# MTX_Tap_an_er_V14_Nopoti.net
KiCad netlist of a schematic drawn in EAGLE
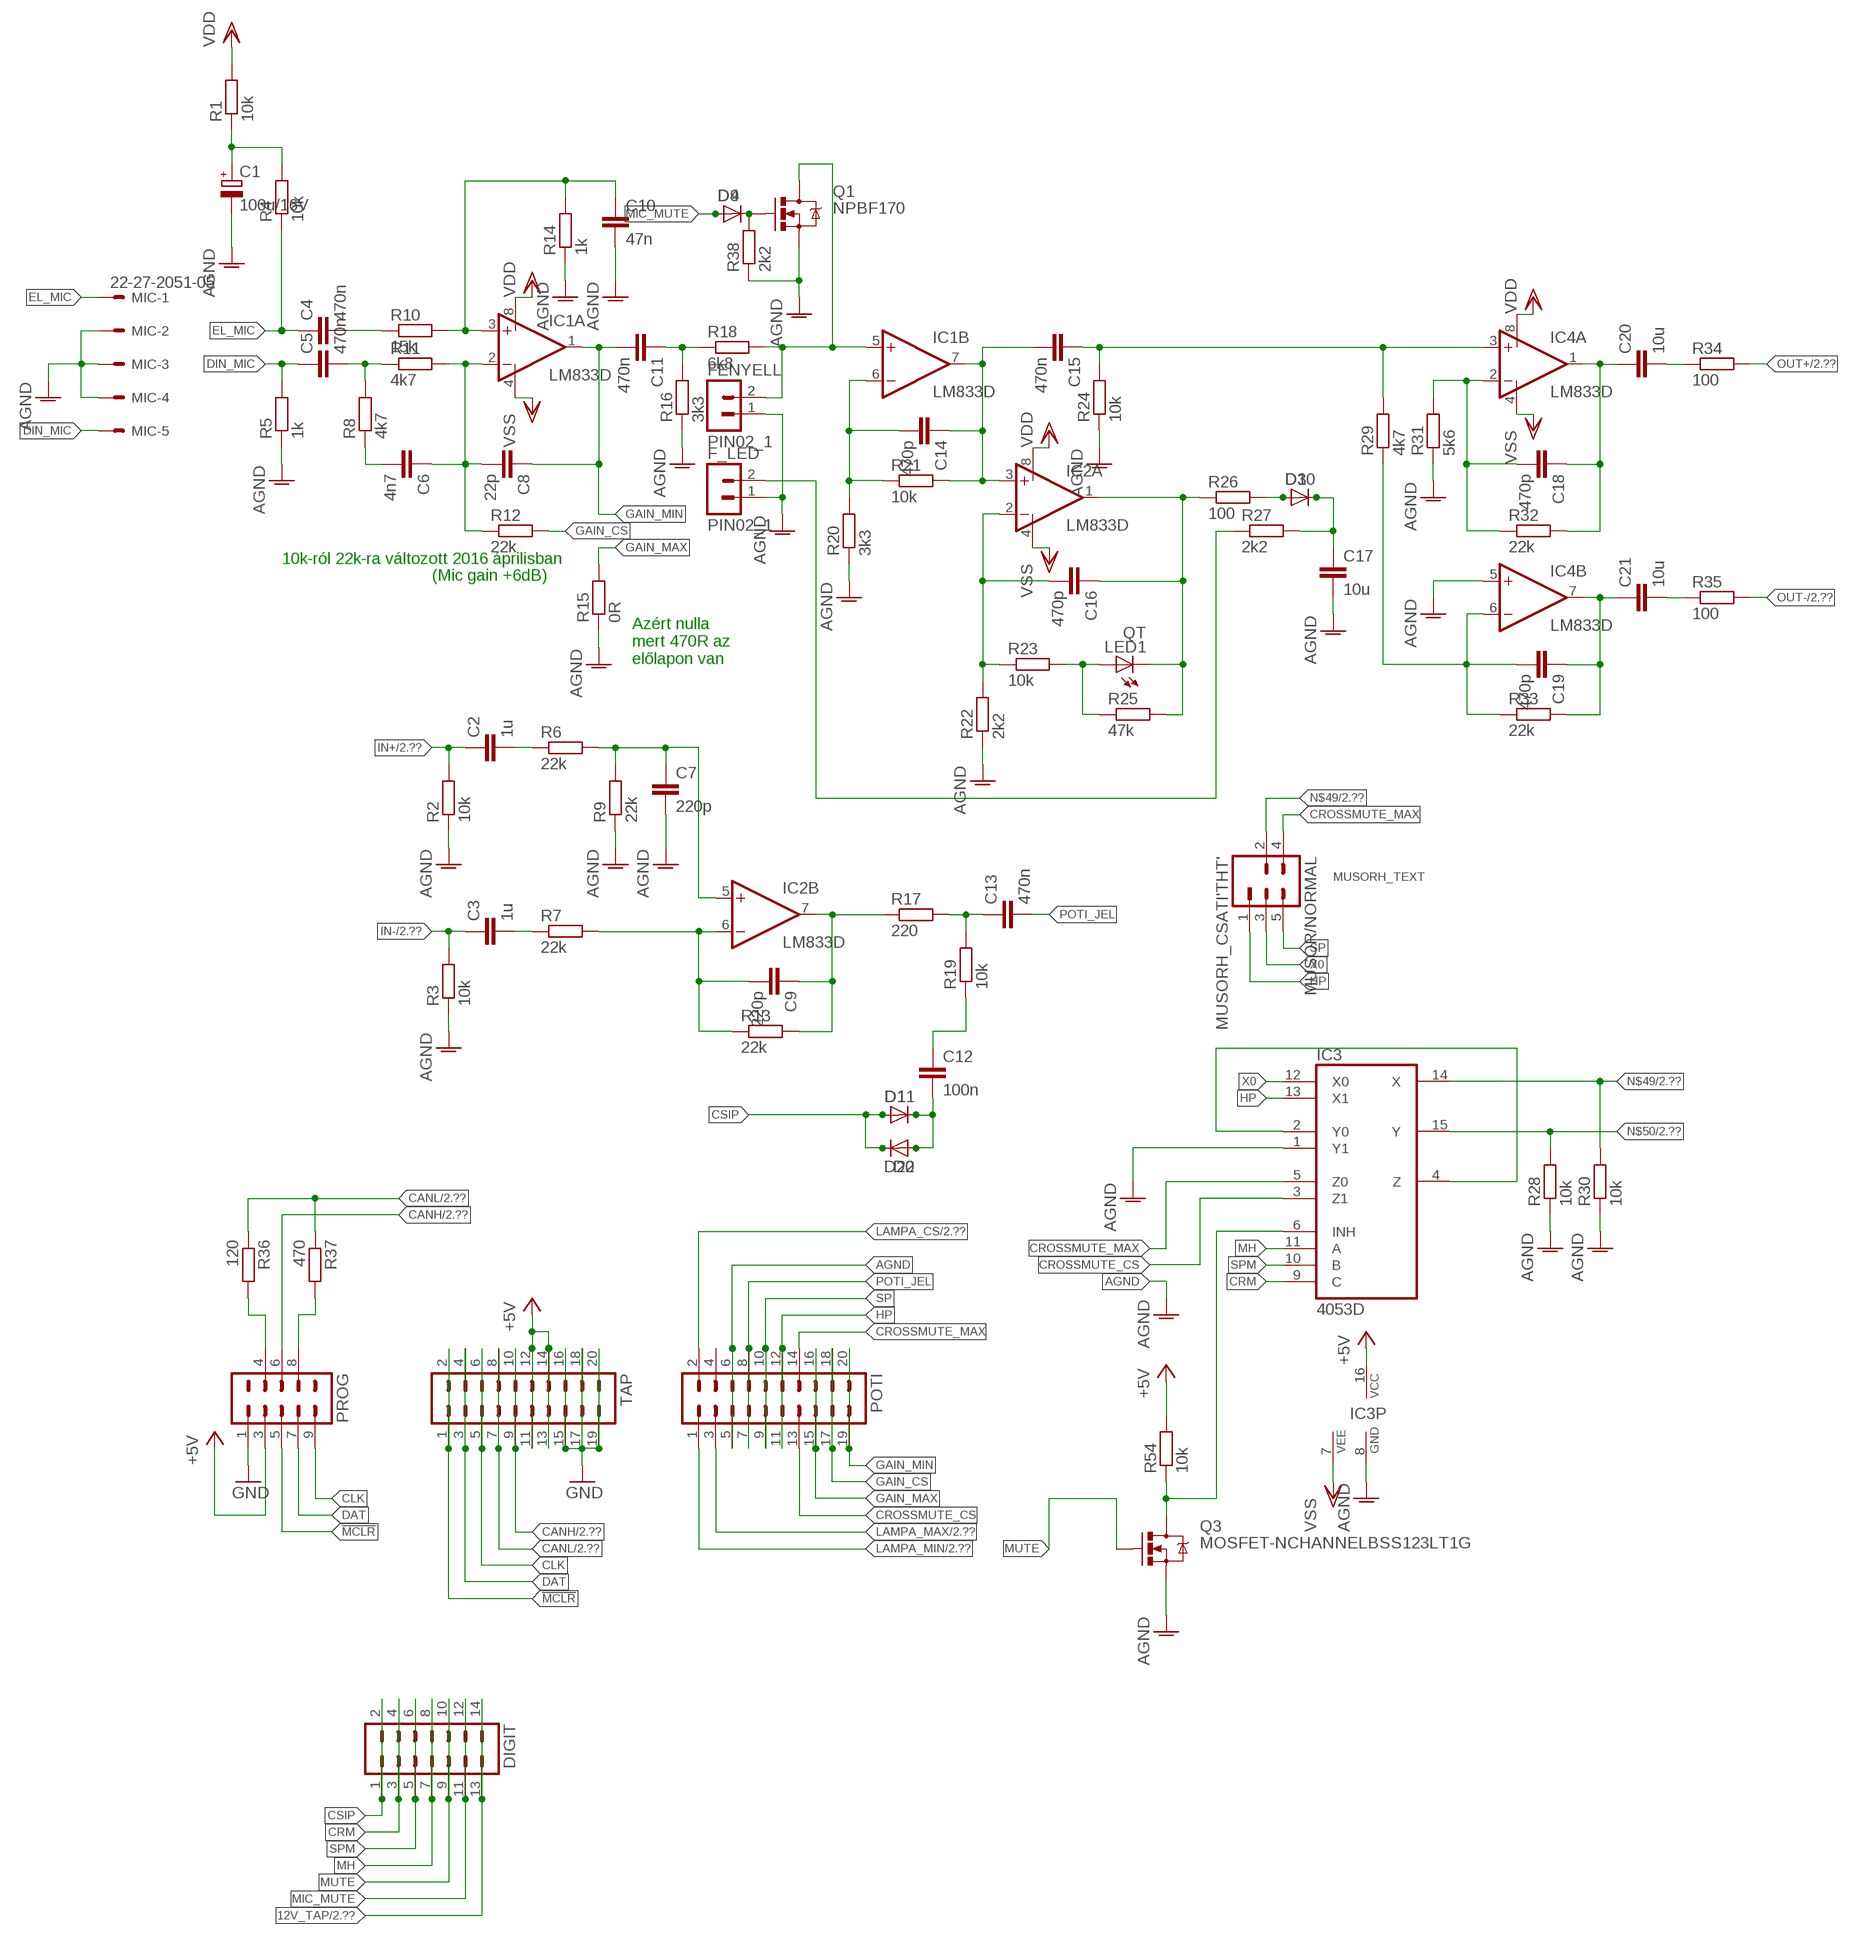
[diagram p0: schematic, sheet 1]
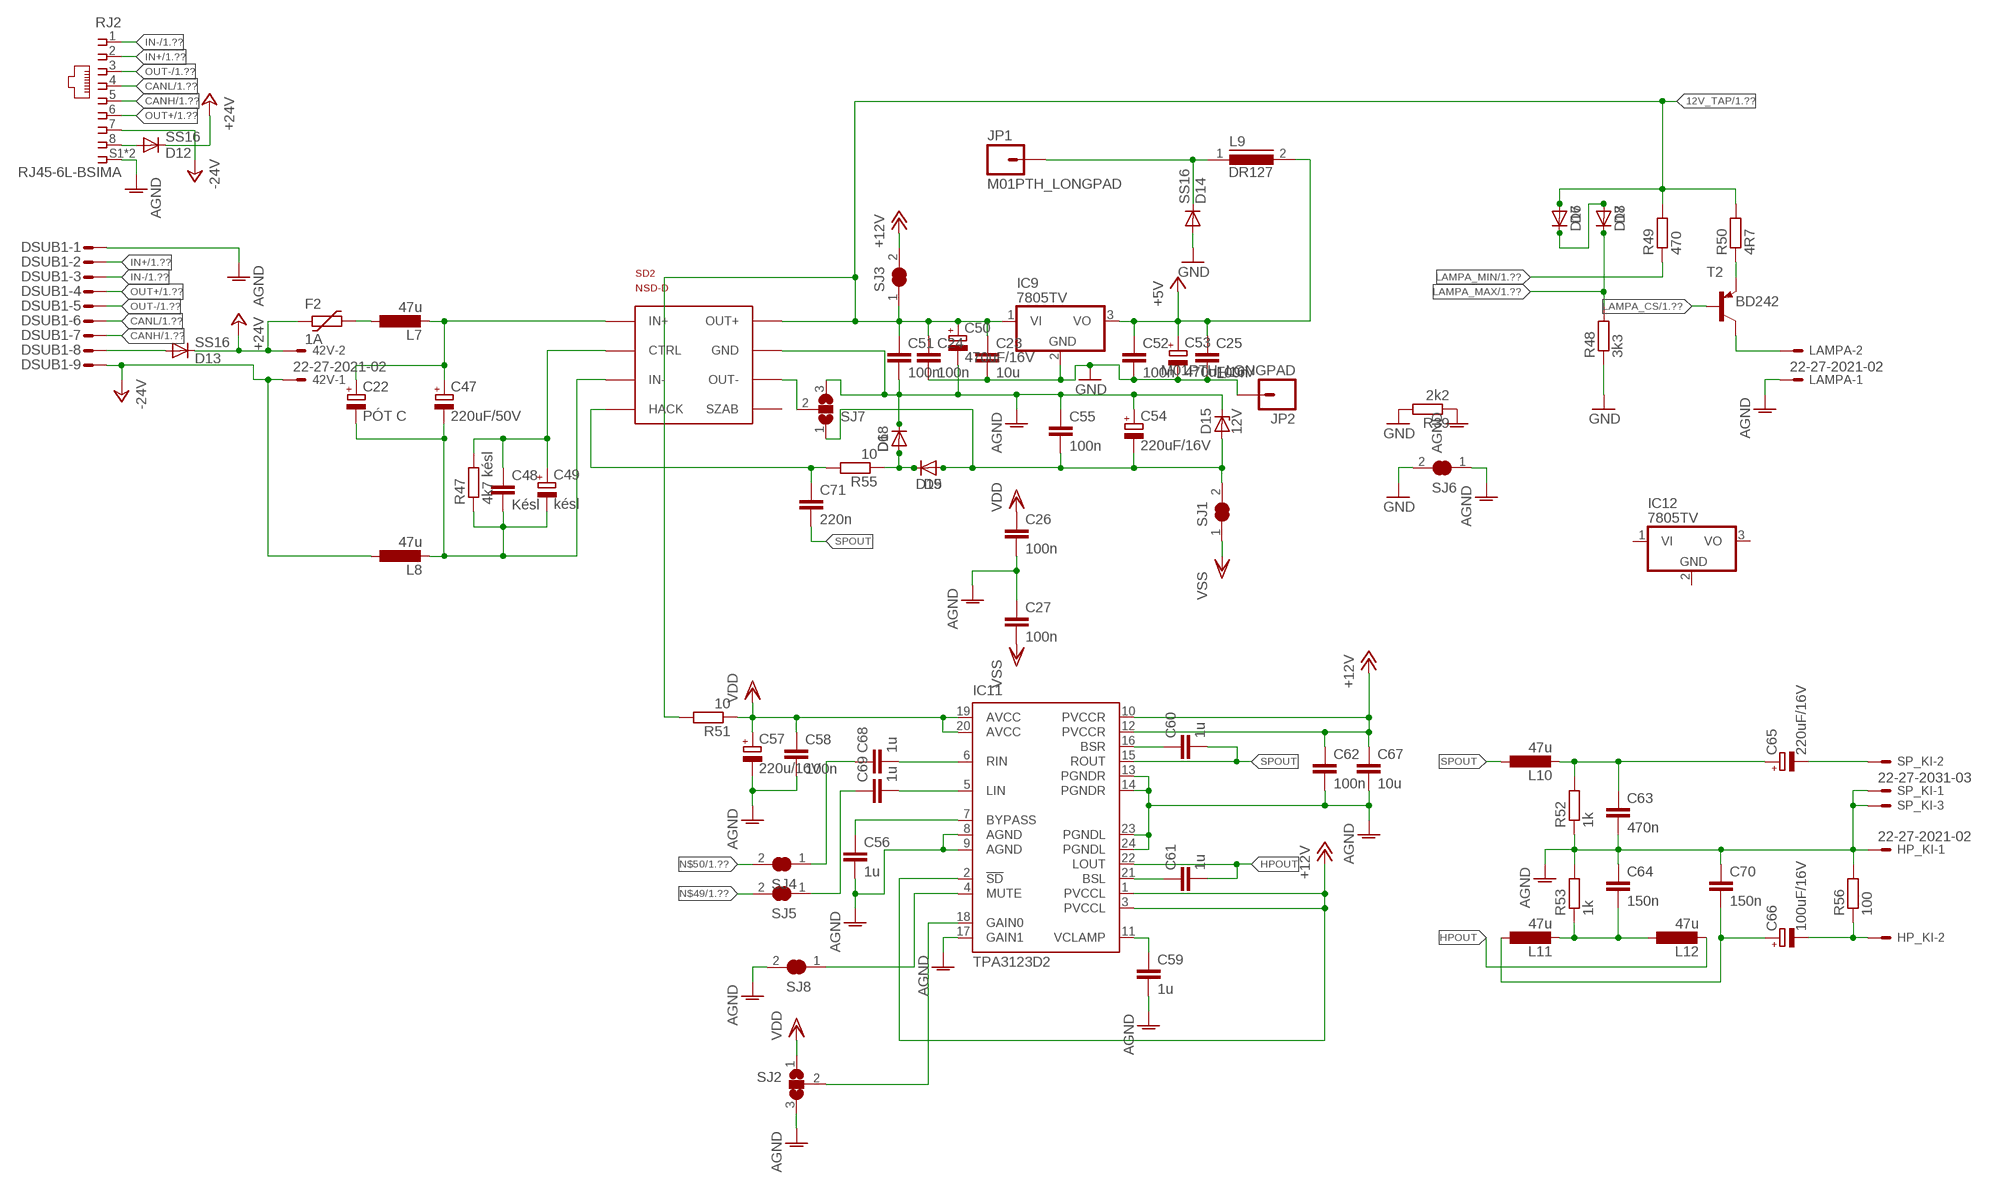
[diagram p1: schematic, sheet 2]

(export (version "E")
  (design (tool "Eeschema 10.0.6"))
  (components
    (comp (ref "C1")
      (value "100u/16V")
      (footprint "eagle-import:E2,5-5")
      (libsource (lib "eagle-import") (part "CPOL-EUE2.5-5"))
    )
    (comp (ref "C2")
      (value "1u")
      (footprint "eagle-import:C0805")
      (libsource (lib "eagle-import") (part "C-EUC0805"))
    )
    (comp (ref "C3")
      (value "1u")
      (footprint "eagle-import:C0805")
      (libsource (lib "eagle-import") (part "C-EUC0805"))
    )
    (comp (ref "C4")
      (value "470n")
      (footprint "eagle-import:C0805")
      (libsource (lib "eagle-import") (part "C-EUC0805"))
    )
    (comp (ref "C5")
      (value "470n")
      (footprint "eagle-import:C0805")
      (libsource (lib "eagle-import") (part "C-EUC0805"))
    )
    (comp (ref "C6")
      (value "4n7")
      (footprint "eagle-import:C0805")
      (libsource (lib "eagle-import") (part "C-EUC0805"))
    )
    (comp (ref "C7")
      (value "220p")
      (footprint "eagle-import:C0805")
      (libsource (lib "eagle-import") (part "C-EUC0805"))
    )
    (comp (ref "C8")
      (value "22p")
      (footprint "eagle-import:C0805")
      (libsource (lib "eagle-import") (part "C-EUC0805"))
    )
    (comp (ref "C9")
      (value "220p")
      (footprint "eagle-import:C0805")
      (libsource (lib "eagle-import") (part "C-EUC0805"))
    )
    (comp (ref "C10")
      (value "47n")
      (footprint "eagle-import:C0805")
      (libsource (lib "eagle-import") (part "C-EUC0805"))
    )
    (comp (ref "C11")
      (value "470n")
      (footprint "eagle-import:C0805")
      (libsource (lib "eagle-import") (part "C-EUC0805"))
    )
    (comp (ref "C12")
      (value "100n")
      (footprint "eagle-import:C0805")
      (libsource (lib "eagle-import") (part "C-EUC0805"))
    )
    (comp (ref "C13")
      (value "470n")
      (footprint "eagle-import:C0805")
      (libsource (lib "eagle-import") (part "C-EUC0805"))
    )
    (comp (ref "C14")
      (value "470p")
      (footprint "eagle-import:C0805")
      (libsource (lib "eagle-import") (part "C-EUC0805"))
    )
    (comp (ref "C15")
      (value "470n")
      (footprint "eagle-import:C0805")
      (libsource (lib "eagle-import") (part "C-EUC0805"))
    )
    (comp (ref "C16")
      (value "470p")
      (footprint "eagle-import:C0805")
      (libsource (lib "eagle-import") (part "C-EUC0805"))
    )
    (comp (ref "C17")
      (value "10u")
      (footprint "eagle-import:C0805")
      (libsource (lib "eagle-import") (part "C-EUC0805"))
    )
    (comp (ref "C18")
      (value "470p")
      (footprint "eagle-import:C0805")
      (libsource (lib "eagle-import") (part "C-EUC0805"))
    )
    (comp (ref "C19")
      (value "470p")
      (footprint "eagle-import:C0805")
      (libsource (lib "eagle-import") (part "C-EUC0805"))
    )
    (comp (ref "C20")
      (value "10u")
      (footprint "eagle-import:C0805")
      (libsource (lib "eagle-import") (part "C-EUC0805"))
    )
    (comp (ref "C21")
      (value "10u")
      (footprint "eagle-import:C0805")
      (libsource (lib "eagle-import") (part "C-EUC0805"))
    )
    (comp (ref "D1")
      (value "1N4148")
      (footprint "eagle-import:DGLASSSMD")
      (libsource (lib "eagle-import") (part "DGLASSMD"))
    )
    (comp (ref "D2")
      (value "1N4148")
      (footprint "eagle-import:DGLASSSMD")
      (libsource (lib "eagle-import") (part "DGLASSMD"))
    )
    (comp (ref "D3")
      (value "1N4148")
      (footprint "eagle-import:DGLASSSMD")
      (libsource (lib "eagle-import") (part "DGLASSMD"))
    )
    (comp (ref "D4")
      (value "1N4148")
      (footprint "eagle-import:DGLASSSMD")
      (libsource (lib "eagle-import") (part "DGLASSMD"))
    )
    (comp (ref "D9")
      (value "D0805")
      (footprint "eagle-import:D0805")
      (libsource (lib "eagle-import") (part "D0805"))
    )
    (comp (ref "D10")
      (value "D0805")
      (footprint "eagle-import:D0805")
      (libsource (lib "eagle-import") (part "D0805"))
    )
    (comp (ref "D11")
      (value "D0805")
      (footprint "eagle-import:D0805")
      (libsource (lib "eagle-import") (part "D0805"))
    )
    (comp (ref "D20")
      (value "D0805")
      (footprint "eagle-import:D0805")
      (libsource (lib "eagle-import") (part "D0805"))
    )
    (comp (ref "DIGIT")
      (value "MA07-2")
      (footprint "eagle-import:MA07-2")
      (libsource (lib "eagle-import") (part "MA07-2"))
    )
    (comp (ref "FENYELL")
      (value "PIN02_1")
      (footprint "eagle-import:PIN02_1")
      (libsource (lib "eagle-import") (part "PIN02_1"))
    )
    (comp (ref "F_LED")
      (value "PIN02_1")
      (footprint "eagle-import:PIN02_1")
      (libsource (lib "eagle-import") (part "PIN02_1"))
    )
    (comp (ref "IC1")
      (value "LM833D")
      (footprint "eagle-import:SO08")
      (libsource (lib "eagle-import") (part "LM833D"))
    )
    (comp (ref "IC2")
      (value "LM833D")
      (footprint "eagle-import:SO08")
      (libsource (lib "eagle-import") (part "LM833D"))
    )
    (comp (ref "IC3")
      (value "4053D")
      (footprint "eagle-import:SO16")
      (libsource (lib "eagle-import") (part "4053D"))
    )
    (comp (ref "IC4")
      (value "LM833D")
      (footprint "eagle-import:SO08")
      (libsource (lib "eagle-import") (part "LM833D"))
    )
    (comp (ref "LED1")
      (value "QT")
      (footprint "eagle-import:LED3MM")
      (libsource (lib "eagle-import") (part "LED3MM"))
    )
    (comp (ref "MIC")
      (value "22-27-2051-05")
      (footprint "eagle-import:6410-05")
      (libsource (lib "eagle-import") (part "22-?-0527-2051"))
    )
    (comp (ref "MUSOR/NORMAL")
      (value "MUSORH_CSATI'THT'")
      (footprint "eagle-import:MUSORH_CSATI")
      (libsource (lib "eagle-import") (part "MUSORH_CSATI'THT'"))
    )
    (comp (ref "POTI")
      (value "MA10-2")
      (footprint "eagle-import:MA10-2")
      (libsource (lib "eagle-import") (part "MA10-2"))
    )
    (comp (ref "PROG")
      (value "CN_CANTAN")
      (footprint "eagle-import:CN_CANTAN")
      (libsource (lib "eagle-import") (part "CN_CANTAN"))
    )
    (comp (ref "Q1")
      (value "NPBF170")
      (footprint "eagle-import:SOT23")
      (libsource (lib "eagle-import") (part "MOSFET-NCHANNELBSS138"))
    )
    (comp (ref "Q3")
      (value "MOSFET-NCHANNELBSS123LT1G")
      (footprint "eagle-import:SOT23")
      (libsource (lib "eagle-import") (part "MOSFET-NCHANNELBSS123LT1G"))
    )
    (comp (ref "R1")
      (value "10k")
      (footprint "eagle-import:R0805")
      (libsource (lib "eagle-import") (part "R-EU_R0805"))
    )
    (comp (ref "R2")
      (value "10k")
      (footprint "eagle-import:R0805")
      (libsource (lib "eagle-import") (part "R-EU_R0805"))
    )
    (comp (ref "R3")
      (value "10k")
      (footprint "eagle-import:R0805")
      (libsource (lib "eagle-import") (part "R-EU_R0805"))
    )
    (comp (ref "R4")
      (value "10k")
      (footprint "eagle-import:R0805")
      (libsource (lib "eagle-import") (part "R-EU_R0805"))
    )
    (comp (ref "R5")
      (value "1k")
      (footprint "eagle-import:R0805")
      (libsource (lib "eagle-import") (part "R-EU_R0805"))
    )
    (comp (ref "R6")
      (value "22k")
      (footprint "eagle-import:R0805")
      (libsource (lib "eagle-import") (part "R-EU_R0805"))
    )
    (comp (ref "R7")
      (value "22k")
      (footprint "eagle-import:R0805")
      (libsource (lib "eagle-import") (part "R-EU_R0805"))
    )
    (comp (ref "R8")
      (value "4k7")
      (footprint "eagle-import:R0805")
      (libsource (lib "eagle-import") (part "R-EU_R0805"))
    )
    (comp (ref "R9")
      (value "22k")
      (footprint "eagle-import:R0805")
      (libsource (lib "eagle-import") (part "R-EU_R0805"))
    )
    (comp (ref "R10")
      (value "15k")
      (footprint "eagle-import:R0805")
      (libsource (lib "eagle-import") (part "R-EU_R0805"))
    )
    (comp (ref "R11")
      (value "4k7")
      (footprint "eagle-import:R0805")
      (libsource (lib "eagle-import") (part "R-EU_R0805"))
    )
    (comp (ref "R12")
      (value "22k")
      (footprint "eagle-import:R0805")
      (libsource (lib "eagle-import") (part "R-EU_R0805"))
    )
    (comp (ref "R13")
      (value "22k")
      (footprint "eagle-import:R0805")
      (libsource (lib "eagle-import") (part "R-EU_R0805"))
    )
    (comp (ref "R14")
      (value "1k")
      (footprint "eagle-import:R0805")
      (libsource (lib "eagle-import") (part "R-EU_R0805"))
    )
    (comp (ref "R15")
      (value "0R")
      (footprint "eagle-import:R0805")
      (libsource (lib "eagle-import") (part "R-EU_R0805"))
    )
    (comp (ref "R16")
      (value "3k3")
      (footprint "eagle-import:R0805")
      (libsource (lib "eagle-import") (part "R-EU_R0805"))
    )
    (comp (ref "R17")
      (value "220")
      (footprint "eagle-import:R0805")
      (libsource (lib "eagle-import") (part "R-EU_R0805"))
    )
    (comp (ref "R18")
      (value "6k8")
      (footprint "eagle-import:R0805")
      (libsource (lib "eagle-import") (part "R-EU_R0805"))
    )
    (comp (ref "R19")
      (value "10k")
      (footprint "eagle-import:R0805")
      (libsource (lib "eagle-import") (part "R-EU_R0805"))
    )
    (comp (ref "R20")
      (value "3k3")
      (footprint "eagle-import:R0805")
      (libsource (lib "eagle-import") (part "R-EU_R0805"))
    )
    (comp (ref "R21")
      (value "10k")
      (footprint "eagle-import:R0805")
      (libsource (lib "eagle-import") (part "R-EU_R0805"))
    )
    (comp (ref "R22")
      (value "2k2")
      (footprint "eagle-import:R0805")
      (libsource (lib "eagle-import") (part "R-EU_R0805"))
    )
    (comp (ref "R23")
      (value "10k")
      (footprint "eagle-import:R0805")
      (libsource (lib "eagle-import") (part "R-EU_R0805"))
    )
    (comp (ref "R24")
      (value "10k")
      (footprint "eagle-import:R0805")
      (libsource (lib "eagle-import") (part "R-EU_R0805"))
    )
    (comp (ref "R25")
      (value "47k")
      (footprint "eagle-import:R0805")
      (libsource (lib "eagle-import") (part "R-EU_R0805"))
    )
    (comp (ref "R26")
      (value "100")
      (footprint "eagle-import:R0805")
      (libsource (lib "eagle-import") (part "R-EU_R0805"))
    )
    (comp (ref "R27")
      (value "2k2")
      (footprint "eagle-import:R0805")
      (libsource (lib "eagle-import") (part "R-EU_R0805"))
    )
    (comp (ref "R28")
      (value "10k")
      (footprint "eagle-import:R0805")
      (libsource (lib "eagle-import") (part "R-EU_R0805"))
    )
    (comp (ref "R29")
      (value "4k7")
      (footprint "eagle-import:R0805")
      (libsource (lib "eagle-import") (part "R-EU_R0805"))
    )
    (comp (ref "R30")
      (value "10k")
      (footprint "eagle-import:R0805")
      (libsource (lib "eagle-import") (part "R-EU_R0805"))
    )
    (comp (ref "R31")
      (value "5k6")
      (footprint "eagle-import:R0805")
      (libsource (lib "eagle-import") (part "R-EU_R0805"))
    )
    (comp (ref "R32")
      (value "22k")
      (footprint "eagle-import:R0805")
      (libsource (lib "eagle-import") (part "R-EU_R0805"))
    )
    (comp (ref "R33")
      (value "22k")
      (footprint "eagle-import:R0805")
      (libsource (lib "eagle-import") (part "R-EU_R0805"))
    )
    (comp (ref "R34")
      (value "100")
      (footprint "eagle-import:R0805")
      (libsource (lib "eagle-import") (part "R-EU_R0805"))
    )
    (comp (ref "R35")
      (value "100")
      (footprint "eagle-import:R0805")
      (libsource (lib "eagle-import") (part "R-EU_R0805"))
    )
    (comp (ref "R36")
      (value "120")
      (footprint "eagle-import:R0805")
      (libsource (lib "eagle-import") (part "R-EU_R0805"))
    )
    (comp (ref "R37")
      (value "470")
      (footprint "eagle-import:R0805")
      (libsource (lib "eagle-import") (part "R-EU_R0805"))
    )
    (comp (ref "R38")
      (value "2k2")
      (footprint "eagle-import:R0805")
      (libsource (lib "eagle-import") (part "R-EU_R0805"))
    )
    (comp (ref "R54")
      (value "10k")
      (footprint "eagle-import:R0805")
      (libsource (lib "eagle-import") (part "R-EU_R0805"))
    )
    (comp (ref "TAP")
      (value "MA10-2")
      (footprint "eagle-import:MA10-2")
      (libsource (lib "eagle-import") (part "MA10-2"))
    )
    (comp (ref "U$1")
      (value "MUSORH_TEXT")
      (footprint "eagle-import:MUSORH_TEXT")
      (libsource (lib "eagle-import") (part "MUSORH_TEXT"))
    )
    (comp (ref "42V")
      (value "22-27-2021-02")
      (footprint "eagle-import:6410-02")
      (libsource (lib "eagle-import") (part "22-?-0227-2021"))
    )
    (comp (ref "C22")
      (value "PÓT C")
      (footprint "eagle-import:E3,5-8")
      (libsource (lib "eagle-import") (part "CPOL-EUE3.5-8"))
    )
    (comp (ref "C23")
      (value "10u")
      (footprint "eagle-import:C0805")
      (libsource (lib "eagle-import") (part "C-EUC0805"))
    )
    (comp (ref "C24")
      (value "100n")
      (footprint "eagle-import:C0805")
      (libsource (lib "eagle-import") (part "C-EUC0805"))
    )
    (comp (ref "C25")
      (value "100n")
      (footprint "eagle-import:C0805")
      (libsource (lib "eagle-import") (part "C-EUC0805"))
    )
    (comp (ref "C26")
      (value "100n")
      (footprint "eagle-import:C0805")
      (libsource (lib "eagle-import") (part "C-EUC0805"))
    )
    (comp (ref "C27")
      (value "100n")
      (footprint "eagle-import:C0805")
      (libsource (lib "eagle-import") (part "C-EUC0805"))
    )
    (comp (ref "C47")
      (value "220uF/50V")
      (footprint "eagle-import:E3,5-8")
      (libsource (lib "eagle-import") (part "CPOL-EUE3.5-8"))
    )
    (comp (ref "C48")
      (value "Késl")
      (footprint "eagle-import:C0805")
      (libsource (lib "eagle-import") (part "C-EUC0805"))
    )
    (comp (ref "C49")
      (value "késl")
      (footprint "eagle-import:E2,5-5")
      (libsource (lib "eagle-import") (part "CPOL-EUE2.5-5"))
    )
    (comp (ref "C50")
      (value "470uF/16V")
      (footprint "eagle-import:E3,5-8")
      (libsource (lib "eagle-import") (part "CPOL-EUE3.5-8"))
    )
    (comp (ref "C51")
      (value "100n")
      (footprint "eagle-import:C0805")
      (libsource (lib "eagle-import") (part "C-EUC0805"))
    )
    (comp (ref "C52")
      (value "100n")
      (footprint "eagle-import:C0805")
      (libsource (lib "eagle-import") (part "C-EUC0805"))
    )
    (comp (ref "C53")
      (value "470uF/16V")
      (footprint "eagle-import:E3,5-8")
      (libsource (lib "eagle-import") (part "CPOL-EUE3.5-8"))
    )
    (comp (ref "C54")
      (value "220uF/16V")
      (footprint "eagle-import:E2,5-7")
      (libsource (lib "eagle-import") (part "CPOL-EUE2.5-7"))
    )
    (comp (ref "C55")
      (value "100n")
      (footprint "eagle-import:C0805")
      (libsource (lib "eagle-import") (part "C-EUC0805"))
    )
    (comp (ref "C56")
      (value "1u")
      (footprint "eagle-import:C0805")
      (libsource (lib "eagle-import") (part "C-EUC0805"))
    )
    (comp (ref "C57")
      (value "220u/16V")
      (footprint "eagle-import:E2,5-7")
      (libsource (lib "eagle-import") (part "CPOL-EUE2.5-7"))
    )
    (comp (ref "C58")
      (value "100n")
      (footprint "eagle-import:C0805")
      (libsource (lib "eagle-import") (part "C-EUC0805"))
    )
    (comp (ref "C59")
      (value "1u")
      (footprint "eagle-import:C0805")
      (libsource (lib "eagle-import") (part "C-EUC0805"))
    )
    (comp (ref "C60")
      (value "1u")
      (footprint "eagle-import:C0805")
      (libsource (lib "eagle-import") (part "C-EUC0805"))
    )
    (comp (ref "C61")
      (value "1u")
      (footprint "eagle-import:C0805")
      (libsource (lib "eagle-import") (part "C-EUC0805"))
    )
    (comp (ref "C62")
      (value "100n")
      (footprint "eagle-import:C0805")
      (libsource (lib "eagle-import") (part "C-EUC0805"))
    )
    (comp (ref "C63")
      (value "470n")
      (footprint "eagle-import:C0805")
      (libsource (lib "eagle-import") (part "C-EUC0805"))
    )
    (comp (ref "C64")
      (value "150n")
      (footprint "eagle-import:C0805")
      (libsource (lib "eagle-import") (part "C-EUC0805"))
    )
    (comp (ref "C65")
      (value "220uF/16V")
      (footprint "eagle-import:E2,5-7")
      (libsource (lib "eagle-import") (part "CPOL-EUE2.5-7"))
    )
    (comp (ref "C66")
      (value "100uF/16V")
      (footprint "eagle-import:E2,5-6")
      (libsource (lib "eagle-import") (part "CPOL-EUE2.5-6"))
    )
    (comp (ref "C67")
      (value "10u")
      (footprint "eagle-import:C0805")
      (libsource (lib "eagle-import") (part "C-EUC0805"))
    )
    (comp (ref "C68")
      (value "1u")
      (footprint "eagle-import:C0805")
      (libsource (lib "eagle-import") (part "C-EUC0805"))
    )
    (comp (ref "C69")
      (value "1u")
      (footprint "eagle-import:C0805")
      (libsource (lib "eagle-import") (part "C-EUC0805"))
    )
    (comp (ref "C70")
      (value "150n")
      (footprint "eagle-import:C0805")
      (libsource (lib "eagle-import") (part "C-EUC0805"))
    )
    (comp (ref "C71")
      (value "220n")
      (footprint "eagle-import:C0805")
      (libsource (lib "eagle-import") (part "C-EUC0805"))
    )
    (comp (ref "D5")
      (value "D0805")
      (footprint "eagle-import:D0805")
      (libsource (lib "eagle-import") (part "D0805"))
    )
    (comp (ref "D6")
      (value "D0805")
      (footprint "eagle-import:D0805")
      (libsource (lib "eagle-import") (part "D0805"))
    )
    (comp (ref "D7")
      (value "D0805")
      (footprint "eagle-import:D0805")
      (libsource (lib "eagle-import") (part "D0805"))
    )
    (comp (ref "D8")
      (value "D0805")
      (footprint "eagle-import:D0805")
      (libsource (lib "eagle-import") (part "D0805"))
    )
    (comp (ref "D12")
      (value "SS16")
      (footprint "eagle-import:DO-214AC")
      (libsource (lib "eagle-import") (part "DIODE-DO-214AC"))
    )
    (comp (ref "D13")
      (value "SS16")
      (footprint "eagle-import:DO-214AC")
      (libsource (lib "eagle-import") (part "DIODE-DO-214AC"))
    )
    (comp (ref "D14")
      (value "SS16")
      (footprint "eagle-import:DO-214AC")
      (libsource (lib "eagle-import") (part "DIODE-DO-214AC"))
    )
    (comp (ref "D15")
      (value "12V")
      (footprint "eagle-import:SOD80C")
      (libsource (lib "eagle-import") (part "ZENER-DIODESOD80C"))
    )
    (comp (ref "D16")
      (value "1N4148")
      (footprint "eagle-import:DGLASSSMD")
      (libsource (lib "eagle-import") (part "DGLASSMD"))
    )
    (comp (ref "D17")
      (value "1N4148")
      (footprint "eagle-import:DGLASSSMD")
      (libsource (lib "eagle-import") (part "DGLASSMD"))
    )
    (comp (ref "D18")
      (value "1N4148")
      (footprint "eagle-import:DGLASSSMD")
      (libsource (lib "eagle-import") (part "DGLASSMD"))
    )
    (comp (ref "D19")
      (value "1N4148")
      (footprint "eagle-import:DGLASSSMD")
      (libsource (lib "eagle-import") (part "DGLASSMD"))
    )
    (comp (ref "DSUB1")
      (value "M09-182S")
      (footprint "eagle-import:182-009-MALE")
      (libsource (lib "eagle-import") (part "M09?S-182"))
    )
    (comp (ref "F2")
      (value "1A")
      (footprint "eagle-import:PTC1812L")
      (libsource (lib "eagle-import") (part "FUSE_PTC-1812"))
    )
    (comp (ref "HP_KI")
      (value "22-27-2021-02")
      (footprint "eagle-import:6410-02")
      (libsource (lib "eagle-import") (part "22-?-0227-2021"))
    )
    (comp (ref "IC9")
      (value "7805TV")
      (footprint "eagle-import:TO220V")
      (libsource (lib "eagle-import") (part "78TV05"))
    )
    (comp (ref "IC11")
      (value "TPA3123D2")
      (footprint "eagle-import:PWP-TSSOP24")
      (fields (field (name "MPN") "TPA3123D2PWP"))
      (libsource (lib "eagle-import") (part "TPA3123D2"))
    )
    (comp (ref "IC12")
      (value "7805TV")
      (footprint "eagle-import:TO220V")
      (libsource (lib "eagle-import") (part "78TV05"))
    )
    (comp (ref "JP1")
      (value "M01PTH_LONGPAD")
      (footprint "eagle-import:1X01_LONGPAD")
      (libsource (lib "eagle-import") (part "M01PTH_LONGPAD"))
    )
    (comp (ref "JP2")
      (value "M01PTH_LONGPAD")
      (footprint "eagle-import:1X01_LONGPAD")
      (libsource (lib "eagle-import") (part "M01PTH_LONGPAD"))
    )
    (comp (ref "L7")
      (value "47u")
      (footprint "eagle-import:PIS2816")
      (libsource (lib "eagle-import") (part "L-EUPIS2816"))
    )
    (comp (ref "L8")
      (value "47u")
      (footprint "eagle-import:PIS2816")
      (libsource (lib "eagle-import") (part "L-EUPIS2816"))
    )
    (comp (ref "L9")
      (value "DR127")
      (footprint "eagle-import:DR127")
      (libsource (lib "eagle-import") (part "DR127"))
    )
    (comp (ref "L10")
      (value "47u")
      (footprint "eagle-import:PIS2816")
      (libsource (lib "eagle-import") (part "L-EUPIS2816"))
    )
    (comp (ref "L11")
      (value "47u")
      (footprint "eagle-import:PIS2816")
      (libsource (lib "eagle-import") (part "L-EUPIS2816"))
    )
    (comp (ref "L12")
      (value "47u")
      (footprint "eagle-import:PIS2816")
      (libsource (lib "eagle-import") (part "L-EUPIS2816"))
    )
    (comp (ref "LAMPA")
      (value "22-27-2021-02")
      (footprint "eagle-import:6410-02")
      (libsource (lib "eagle-import") (part "22-?-0227-2021"))
    )
    (comp (ref "R39")
      (value "2k2")
      (footprint "eagle-import:R0805")
      (libsource (lib "eagle-import") (part "R-EU_R0805"))
    )
    (comp (ref "R47")
      (value "4k7 késl")
      (footprint "eagle-import:R0805")
      (libsource (lib "eagle-import") (part "R-EU_R0805"))
    )
    (comp (ref "R48")
      (value "3k3")
      (footprint "eagle-import:R0805")
      (libsource (lib "eagle-import") (part "R-EU_R0805"))
    )
    (comp (ref "R49")
      (value "470")
      (footprint "eagle-import:R0805")
      (libsource (lib "eagle-import") (part "R-EU_R0805"))
    )
    (comp (ref "R50")
      (value "4R7")
      (footprint "eagle-import:R0805")
      (libsource (lib "eagle-import") (part "R-EU_R0805"))
    )
    (comp (ref "R51")
      (value "10")
      (footprint "eagle-import:R1210")
      (libsource (lib "eagle-import") (part "R-EU_R1210"))
    )
    (comp (ref "R52")
      (value "1k")
      (footprint "eagle-import:R0805")
      (libsource (lib "eagle-import") (part "R-EU_R0805"))
    )
    (comp (ref "R53")
      (value "1k")
      (footprint "eagle-import:R0805")
      (libsource (lib "eagle-import") (part "R-EU_R0805"))
    )
    (comp (ref "R55")
      (value "10")
      (footprint "eagle-import:R0805")
      (libsource (lib "eagle-import") (part "R-EU_R0805"))
    )
    (comp (ref "R56")
      (value "100")
      (footprint "eagle-import:R0805")
      (libsource (lib "eagle-import") (part "R-EU_R0805"))
    )
    (comp (ref "RJ2")
      (value "RJ45-6L-BSIMA")
      (footprint "eagle-import:RJ45")
      (fields (field (name "MPN") "RJ45-6L-B"))
      (libsource (lib "eagle-import") (part "RJ45SIMA-6L-B"))
    )
    (comp (ref "SD2")
      (value "NSD-D")
      (footprint "eagle-import:NSD-D")
      (libsource (lib "eagle-import") (part "NSD-D"))
    )
    (comp (ref "SJ1")
      (value "SOLDERJUMPER_CLOSED")
      (footprint "eagle-import:SOLDERJUMPER_CLOSEDWIRE")
      (libsource (lib "eagle-import") (part "SOLDERJUMPER_CLOSED"))
    )
    (comp (ref "SJ2")
      (value "SJ2WW12")
      (footprint "eagle-import:SJ_2W_12")
      (libsource (lib "eagle-import") (part "SJ2WW12"))
    )
    (comp (ref "SJ3")
      (value "SOLDERJUMPER_CLOSED")
      (footprint "eagle-import:SOLDERJUMPER_CLOSEDWIRE")
      (libsource (lib "eagle-import") (part "SOLDERJUMPER_CLOSED"))
    )
    (comp (ref "SJ4")
      (value "SOLDERJUMPER_CLOSED")
      (footprint "eagle-import:SOLDERJUMPER_CLOSEDWIRE")
      (libsource (lib "eagle-import") (part "SOLDERJUMPER_CLOSED"))
    )
    (comp (ref "SJ5")
      (value "SOLDERJUMPER_CLOSED")
      (footprint "eagle-import:SOLDERJUMPER_CLOSEDWIRE")
      (libsource (lib "eagle-import") (part "SOLDERJUMPER_CLOSED"))
    )
    (comp (ref "SJ6")
      (value "SOLDERJUMPER_CLOSED")
      (footprint "eagle-import:SOLDERJUMPER_CLOSEDWIRE")
      (libsource (lib "eagle-import") (part "SOLDERJUMPER_CLOSED"))
    )
    (comp (ref "SJ7")
      (value "SJ2WW23")
      (footprint "eagle-import:SJ_2W_23")
      (libsource (lib "eagle-import") (part "SJ2WW23"))
    )
    (comp (ref "SJ8")
      (value "SOLDERJUMPER_CLOSED")
      (footprint "eagle-import:SOLDERJUMPER_CLOSEDWIRE")
      (libsource (lib "eagle-import") (part "SOLDERJUMPER_CLOSED"))
    )
    (comp (ref "SP_KI")
      (value "22-27-2031-03")
      (footprint "eagle-import:6410-03")
      (libsource (lib "eagle-import") (part "22-?-0327-2031"))
    )
    (comp (ref "T2")
      (value "BD242")
      (footprint "eagle-import:TO220V")
      (libsource (lib "eagle-import") (part "-PNP-TO220V"))
    )
  )
  (nets
    (net (code "1") (name "+5V") (class "Default")
      (node (ref "C25") (pin "1") (pinfunction "1_1") (pintype "passive"))
      (node (ref "C52") (pin "1") (pinfunction "1_1") (pintype "passive"))
      (node (ref "C53") (pin "+") (pinfunction "+_+") (pintype "passive"))
      (node (ref "IC3") (pin "16") (pinfunction "VCC_16") (pintype "power_in"))
      (node (ref "IC9") (pin "3") (pinfunction "VO_3") (pintype "passive"))
      (node (ref "L9") (pin "2") (pinfunction "2_2") (pintype "passive"))
      (node (ref "PROG") (pin "3") (pinfunction "3_3") (pintype "passive"))
      (node (ref "R54") (pin "2") (pinfunction "2_2") (pintype "passive"))
      (node (ref "TAP") (pin "11") (pinfunction "11_11") (pintype "passive"))
      (node (ref "TAP") (pin "12") (pinfunction "12_12") (pintype "passive"))
      (node (ref "TAP") (pin "13") (pinfunction "13_13") (pintype "passive"))
      (node (ref "TAP") (pin "14") (pinfunction "14_14") (pintype "passive"))
    )
    (net (code "2") (name "+12V") (class "Default")
      (node (ref "C62") (pin "1") (pinfunction "1_1") (pintype "passive"))
      (node (ref "C67") (pin "1") (pinfunction "1_1") (pintype "passive"))
      (node (ref "IC11") (pin "1") (pinfunction "PVCCL_1") (pintype "input"))
      (node (ref "IC11") (pin "10") (pinfunction "PVCCR_10") (pintype "input"))
      (node (ref "IC11") (pin "12") (pinfunction "PVCCR_12") (pintype "input"))
      (node (ref "IC11") (pin "2") (pinfunction "~{SD}_2") (pintype "input"))
      (node (ref "IC11") (pin "3") (pinfunction "PVCCL_3") (pintype "input"))
      (node (ref "SJ3") (pin "2") (pinfunction "2_2") (pintype "passive"))
    )
    (net (code "3") (name "+24V") (class "Default")
      (node (ref "42V") (pin "2") (pinfunction "S_2") (pintype "passive"))
      (node (ref "D12") (pin "1") (pinfunction "C_1") (pintype "passive"))
      (node (ref "D13") (pin "1") (pinfunction "C_1") (pintype "passive"))
      (node (ref "F2") (pin "1") (pinfunction "1_1") (pintype "passive"))
    )
    (net (code "4") (name "-24V") (class "Default")
      (node (ref "42V") (pin "1") (pinfunction "S_1") (pintype "passive"))
      (node (ref "DSUB1") (pin "9") (pinfunction "M_9") (pintype "passive"))
      (node (ref "L8") (pin "1") (pinfunction "1_1") (pintype "passive"))
      (node (ref "RJ2") (pin "7") (pinfunction "7_7") (pintype "passive"))
    )
    (net (code "5") (name "12V_TAP") (class "Default")
      (node (ref "C23") (pin "1") (pinfunction "1_1") (pintype "passive"))
      (node (ref "C24") (pin "1") (pinfunction "1_1") (pintype "passive"))
      (node (ref "C50") (pin "+") (pinfunction "+_+") (pintype "passive"))
      (node (ref "C51") (pin "1") (pinfunction "1_1") (pintype "passive"))
      (node (ref "D16") (pin "P$1") (pinfunction "A_P$1") (pintype "passive"))
      (node (ref "D7") (pin "1") (pinfunction "A_1") (pintype "passive"))
      (node (ref "DIGIT") (pin "13") (pinfunction "13_13") (pintype "passive"))
      (node (ref "DIGIT") (pin "14") (pinfunction "14_14") (pintype "passive"))
      (node (ref "IC9") (pin "1") (pinfunction "VI_1") (pintype "input"))
      (node (ref "R49") (pin "2") (pinfunction "2_2") (pintype "passive"))
      (node (ref "R50") (pin "2") (pinfunction "2_2") (pintype "passive"))
      (node (ref "R51") (pin "2") (pinfunction "2_2") (pintype "passive"))
      (node (ref "SD2") (pin "OUT+") (pinfunction "OUT+_OUT+") (pintype "bidirectional"))
      (node (ref "SJ3") (pin "1") (pinfunction "1_1") (pintype "passive"))
    )
    (net (code "6") (name "AGND") (class "Default")
      (node (ref "C1") (pin "-") (pinfunction "-_-") (pintype "passive"))
      (node (ref "C10") (pin "2") (pinfunction "2_2") (pintype "passive"))
      (node (ref "C17") (pin "2") (pinfunction "2_2") (pintype "passive"))
      (node (ref "C26") (pin "2") (pinfunction "2_2") (pintype "passive"))
      (node (ref "C27") (pin "1") (pinfunction "1_1") (pintype "passive"))
      (node (ref "C50") (pin "-") (pinfunction "-_-") (pintype "passive"))
      (node (ref "C51") (pin "2") (pinfunction "2_2") (pintype "passive"))
      (node (ref "C54") (pin "+") (pinfunction "+_+") (pintype "passive"))
      (node (ref "C55") (pin "1") (pinfunction "1_1") (pintype "passive"))
      (node (ref "C56") (pin "2") (pinfunction "2_2") (pintype "passive"))
      (node (ref "C57") (pin "-") (pinfunction "-_-") (pintype "passive"))
      (node (ref "C58") (pin "2") (pinfunction "2_2") (pintype "passive"))
      (node (ref "C59") (pin "2") (pinfunction "2_2") (pintype "passive"))
      (node (ref "C62") (pin "2") (pinfunction "2_2") (pintype "passive"))
      (node (ref "C63") (pin "2") (pinfunction "2_2") (pintype "passive"))
      (node (ref "C64") (pin "1") (pinfunction "1_1") (pintype "passive"))
      (node (ref "C67") (pin "2") (pinfunction "2_2") (pintype "passive"))
      (node (ref "C7") (pin "2") (pinfunction "2_2") (pintype "passive"))
      (node (ref "C70") (pin "1") (pinfunction "1_1") (pintype "passive"))
      (node (ref "D15") (pin "C") (pinfunction "C_C") (pintype "passive"))
      (node (ref "D18") (pin "P$2") (pinfunction "C_P$2") (pintype "passive"))
      (node (ref "D6") (pin "2") (pinfunction "C_2") (pintype "passive"))
      (node (ref "DSUB1") (pin "1") (pinfunction "M_1") (pintype "passive"))
      (node (ref "FENYELL") (pin "1") (pinfunction "1_1") (pintype "passive"))
      (node (ref "F_LED") (pin "1") (pinfunction "1_1") (pintype "passive"))
      (node (ref "HP_KI") (pin "1") (pinfunction "S_1") (pintype "passive"))
      (node (ref "IC11") (pin "13") (pinfunction "PGNDR_13") (pintype "input"))
      (node (ref "IC11") (pin "14") (pinfunction "PGNDR_14") (pintype "input"))
      (node (ref "IC11") (pin "17") (pinfunction "GAIN1_17") (pintype "input"))
      (node (ref "IC11") (pin "23") (pinfunction "PGNDL_23") (pintype "input"))
      (node (ref "IC11") (pin "24") (pinfunction "PGNDL_24") (pintype "input"))
      (node (ref "IC11") (pin "8") (pinfunction "AGND_8") (pintype "input"))
      (node (ref "IC11") (pin "9") (pinfunction "AGND_9") (pintype "input"))
      (node (ref "IC3") (pin "1") (pinfunction "Y1_1") (pintype "bidirectional"))
      (node (ref "IC3") (pin "8") (pinfunction "GND_8") (pintype "power_in"))
      (node (ref "IC4") (pin "5") (pinfunction "+IN_5") (pintype "input"))
      (node (ref "LAMPA") (pin "1") (pinfunction "S_1") (pintype "passive"))
      (node (ref "MIC") (pin "2") (pinfunction "S_2") (pintype "passive"))
      (node (ref "MIC") (pin "3") (pinfunction "S_3") (pintype "passive"))
      (node (ref "MIC") (pin "4") (pinfunction "S_4") (pintype "passive"))
      (node (ref "POTI") (pin "5") (pinfunction "5_5") (pintype "passive"))
      (node (ref "POTI") (pin "6") (pinfunction "6_6") (pintype "passive"))
      (node (ref "Q1") (pin "2") (pinfunction "S_2") (pintype "passive"))
      (node (ref "Q3") (pin "2") (pinfunction "S_2") (pintype "passive"))
      (node (ref "R14") (pin "1") (pinfunction "1_1") (pintype "passive"))
      (node (ref "R15") (pin "1") (pinfunction "1_1") (pintype "passive"))
      (node (ref "R16") (pin "1") (pinfunction "1_1") (pintype "passive"))
      (node (ref "R2") (pin "1") (pinfunction "1_1") (pintype "passive"))
      (node (ref "R20") (pin "1") (pinfunction "1_1") (pintype "passive"))
      (node (ref "R22") (pin "1") (pinfunction "1_1") (pintype "passive"))
      (node (ref "R24") (pin "1") (pinfunction "1_1") (pintype "passive"))
      (node (ref "R28") (pin "1") (pinfunction "1_1") (pintype "passive"))
      (node (ref "R3") (pin "1") (pinfunction "1_1") (pintype "passive"))
      (node (ref "R30") (pin "1") (pinfunction "1_1") (pintype "passive"))
      (node (ref "R31") (pin "1") (pinfunction "1_1") (pintype "passive"))
      (node (ref "R38") (pin "1") (pinfunction "1_1") (pintype "passive"))
      (node (ref "R39") (pin "1") (pinfunction "1_1") (pintype "passive"))
      (node (ref "R5") (pin "1") (pinfunction "1_1") (pintype "passive"))
      (node (ref "R52") (pin "1") (pinfunction "1_1") (pintype "passive"))
      (node (ref "R53") (pin "2") (pinfunction "2_2") (pintype "passive"))
      (node (ref "R56") (pin "2") (pinfunction "2_2") (pintype "passive"))
      (node (ref "R9") (pin "1") (pinfunction "1_1") (pintype "passive"))
      (node (ref "RJ2") (pin "S1") (pinfunction "S_S1") (pintype "passive"))
      (node (ref "RJ2") (pin "S2") (pinfunction "S_S2") (pintype "passive"))
      (node (ref "SD2") (pin "COMMON") (pinfunction "GND_COMMON") (pintype "bidirectional"))
      (node (ref "SJ2") (pin "3") (pinfunction "3_3") (pintype "passive"))
      (node (ref "SJ6") (pin "1") (pinfunction "1_1") (pintype "passive"))
      (node (ref "SJ7") (pin "3") (pinfunction "3_3") (pintype "passive"))
      (node (ref "SJ8") (pin "2") (pinfunction "2_2") (pintype "passive"))
      (node (ref "SP_KI") (pin "1") (pinfunction "S_1") (pintype "passive"))
      (node (ref "SP_KI") (pin "3") (pinfunction "S_3") (pintype "passive"))
    )
    (net (code "7") (name "CANH") (class "Default")
      (node (ref "DSUB1") (pin "7") (pinfunction "M_7") (pintype "passive"))
      (node (ref "PROG") (pin "6") (pinfunction "6_6") (pintype "passive"))
      (node (ref "RJ2") (pin "5") (pinfunction "5_5") (pintype "passive"))
      (node (ref "TAP") (pin "10") (pinfunction "10_10") (pintype "passive"))
      (node (ref "TAP") (pin "9") (pinfunction "9_9") (pintype "passive"))
    )
    (net (code "8") (name "CANL") (class "Default")
      (node (ref "DSUB1") (pin "6") (pinfunction "M_6") (pintype "passive"))
      (node (ref "R36") (pin "1") (pinfunction "1_1") (pintype "passive"))
      (node (ref "R37") (pin "1") (pinfunction "1_1") (pintype "passive"))
      (node (ref "RJ2") (pin "4") (pinfunction "4_4") (pintype "passive"))
      (node (ref "TAP") (pin "7") (pinfunction "7_7") (pintype "passive"))
      (node (ref "TAP") (pin "8") (pinfunction "8_8") (pintype "passive"))
    )
    (net (code "9") (name "CLK") (class "Default")
      (node (ref "PROG") (pin "9") (pinfunction "9_9") (pintype "passive"))
      (node (ref "TAP") (pin "5") (pinfunction "5_5") (pintype "passive"))
      (node (ref "TAP") (pin "6") (pinfunction "6_6") (pintype "passive"))
    )
    (net (code "10") (name "CRM") (class "Default")
      (node (ref "DIGIT") (pin "3") (pinfunction "3_3") (pintype "passive"))
      (node (ref "DIGIT") (pin "4") (pinfunction "4_4") (pintype "passive"))
      (node (ref "IC3") (pin "9") (pinfunction "C_9") (pintype "input"))
    )
    (net (code "11") (name "CROSSMUTE_CS") (class "Default")
      (node (ref "IC3") (pin "3") (pinfunction "Z1_3") (pintype "bidirectional"))
      (node (ref "POTI") (pin "13") (pinfunction "13_13") (pintype "passive"))
    )
    (net (code "12") (name "CROSSMUTE_MAX") (class "Default")
      (node (ref "IC3") (pin "5") (pinfunction "Z0_5") (pintype "bidirectional"))
      (node (ref "MUSOR/NORMAL") (pin "4") (pinfunction "4_4") (pintype "passive"))
      (node (ref "POTI") (pin "14") (pinfunction "14_14") (pintype "passive"))
    )
    (net (code "13") (name "CSIP") (class "Default")
      (node (ref "D1") (pin "P$1") (pinfunction "A_P$1") (pintype "passive"))
      (node (ref "D11") (pin "1") (pinfunction "A_1") (pintype "passive"))
      (node (ref "D2") (pin "P$2") (pinfunction "C_P$2") (pintype "passive"))
      (node (ref "D20") (pin "2") (pinfunction "C_2") (pintype "passive"))
      (node (ref "DIGIT") (pin "1") (pinfunction "1_1") (pintype "passive"))
      (node (ref "DIGIT") (pin "2") (pinfunction "2_2") (pintype "passive"))
    )
    (net (code "14") (name "DAT") (class "Default")
      (node (ref "PROG") (pin "7") (pinfunction "7_7") (pintype "passive"))
      (node (ref "TAP") (pin "3") (pinfunction "3_3") (pintype "passive"))
      (node (ref "TAP") (pin "4") (pinfunction "4_4") (pintype "passive"))
    )
    (net (code "15") (name "DIN_MIC") (class "Default")
      (node (ref "C5") (pin "1") (pinfunction "1_1") (pintype "passive"))
      (node (ref "MIC") (pin "5") (pinfunction "S_5") (pintype "passive"))
      (node (ref "R5") (pin "2") (pinfunction "2_2") (pintype "passive"))
    )
    (net (code "16") (name "EL_MIC") (class "Default")
      (node (ref "C4") (pin "1") (pinfunction "1_1") (pintype "passive"))
      (node (ref "MIC") (pin "1") (pinfunction "S_1") (pintype "passive"))
      (node (ref "R4") (pin "1") (pinfunction "1_1") (pintype "passive"))
    )
    (net (code "17") (name "GAIN_CS") (class "Default")
      (node (ref "POTI") (pin "17") (pinfunction "17_17") (pintype "passive"))
      (node (ref "POTI") (pin "18") (pinfunction "18_18") (pintype "passive"))
      (node (ref "R12") (pin "2") (pinfunction "2_2") (pintype "passive"))
    )
    (net (code "18") (name "GAIN_MAX") (class "Default")
      (node (ref "POTI") (pin "15") (pinfunction "15_15") (pintype "passive"))
      (node (ref "POTI") (pin "16") (pinfunction "16_16") (pintype "passive"))
      (node (ref "R15") (pin "2") (pinfunction "2_2") (pintype "passive"))
    )
    (net (code "19") (name "GAIN_MIN") (class "Default")
      (node (ref "C11") (pin "2") (pinfunction "2_2") (pintype "passive"))
      (node (ref "C8") (pin "1") (pinfunction "1_1") (pintype "passive"))
      (node (ref "IC1") (pin "1") (pinfunction "OUT_1") (pintype "output"))
      (node (ref "POTI") (pin "19") (pinfunction "19_19") (pintype "passive"))
      (node (ref "POTI") (pin "20") (pinfunction "20_20") (pintype "passive"))
    )
    (net (code "20") (name "GND") (class "Default")
      (node (ref "C23") (pin "2") (pinfunction "2_2") (pintype "passive"))
      (node (ref "C24") (pin "2") (pinfunction "2_2") (pintype "passive"))
      (node (ref "C25") (pin "2") (pinfunction "2_2") (pintype "passive"))
      (node (ref "C52") (pin "2") (pinfunction "2_2") (pintype "passive"))
      (node (ref "C53") (pin "-") (pinfunction "-_-") (pintype "passive"))
      (node (ref "D14") (pin "2") (pinfunction "A_2") (pintype "passive"))
      (node (ref "IC9") (pin "2") (pinfunction "GND_2") (pintype "passive"))
      (node (ref "JP2") (pin "1") (pinfunction "1_1") (pintype "passive"))
      (node (ref "PROG") (pin "1") (pinfunction "1_1") (pintype "passive"))
      (node (ref "R39") (pin "2") (pinfunction "2_2") (pintype "passive"))
      (node (ref "R48") (pin "1") (pinfunction "1_1") (pintype "passive"))
      (node (ref "SJ6") (pin "2") (pinfunction "2_2") (pintype "passive"))
      (node (ref "TAP") (pin "15") (pinfunction "15_15") (pintype "passive"))
      (node (ref "TAP") (pin "16") (pinfunction "16_16") (pintype "passive"))
      (node (ref "TAP") (pin "17") (pinfunction "17_17") (pintype "passive"))
      (node (ref "TAP") (pin "18") (pinfunction "18_18") (pintype "passive"))
      (node (ref "TAP") (pin "19") (pinfunction "19_19") (pintype "passive"))
      (node (ref "TAP") (pin "20") (pinfunction "20_20") (pintype "passive"))
    )
    (net (code "21") (name "HP") (class "Default")
      (node (ref "IC3") (pin "13") (pinfunction "X1_13") (pintype "bidirectional"))
      (node (ref "MUSOR/NORMAL") (pin "1") (pinfunction "1_1") (pintype "passive"))
      (node (ref "POTI") (pin "11") (pinfunction "11_11") (pintype "passive"))
      (node (ref "POTI") (pin "12") (pinfunction "12_12") (pintype "passive"))
    )
    (net (code "22") (name "HPOUT") (class "Default")
      (node (ref "C61") (pin "2") (pinfunction "2_2") (pintype "passive"))
      (node (ref "IC11") (pin "22") (pinfunction "LOUT_22") (pintype "output"))
      (node (ref "L12") (pin "2") (pinfunction "2_2") (pintype "passive"))
    )
    (net (code "23") (name "IN+") (class "Default")
      (node (ref "C2") (pin "1") (pinfunction "1_1") (pintype "passive"))
      (node (ref "DSUB1") (pin "2") (pinfunction "M_2") (pintype "passive"))
      (node (ref "R2") (pin "2") (pinfunction "2_2") (pintype "passive"))
      (node (ref "RJ2") (pin "2") (pinfunction "2_2") (pintype "passive"))
    )
    (net (code "24") (name "IN-") (class "Default")
      (node (ref "C3") (pin "1") (pinfunction "1_1") (pintype "passive"))
      (node (ref "DSUB1") (pin "3") (pinfunction "M_3") (pintype "passive"))
      (node (ref "R3") (pin "2") (pinfunction "2_2") (pintype "passive"))
      (node (ref "RJ2") (pin "1") (pinfunction "1_1") (pintype "passive"))
    )
    (net (code "25") (name "LAMPA_CS") (class "Default")
      (node (ref "POTI") (pin "2") (pinfunction "2_2") (pintype "passive"))
      (node (ref "T2") (pin "1") (pinfunction "B_1") (pintype "passive"))
    )
    (net (code "26") (name "LAMPA_MAX") (class "Default")
      (node (ref "D17") (pin "P$2") (pinfunction "C_P$2") (pintype "passive"))
      (node (ref "D8") (pin "2") (pinfunction "C_2") (pintype "passive"))
      (node (ref "POTI") (pin "3") (pinfunction "3_3") (pintype "passive"))
      (node (ref "R48") (pin "2") (pinfunction "2_2") (pintype "passive"))
    )
    (net (code "27") (name "LAMPA_MIN") (class "Default")
      (node (ref "POTI") (pin "1") (pinfunction "1_1") (pintype "passive"))
      (node (ref "R49") (pin "1") (pinfunction "1_1") (pintype "passive"))
    )
    (net (code "28") (name "MH") (class "Default")
      (node (ref "DIGIT") (pin "7") (pinfunction "7_7") (pintype "passive"))
      (node (ref "DIGIT") (pin "8") (pinfunction "8_8") (pintype "passive"))
      (node (ref "IC3") (pin "11") (pinfunction "A_11") (pintype "input"))
    )
    (net (code "29") (name "MIC_MUTE") (class "Default")
      (node (ref "D4") (pin "P$1") (pinfunction "A_P$1") (pintype "passive"))
      (node (ref "D9") (pin "1") (pinfunction "A_1") (pintype "passive"))
      (node (ref "DIGIT") (pin "11") (pinfunction "11_11") (pintype "passive"))
      (node (ref "DIGIT") (pin "12") (pinfunction "12_12") (pintype "passive"))
    )
    (net (code "30") (name "MUTE") (class "Default")
      (node (ref "DIGIT") (pin "10") (pinfunction "10_10") (pintype "passive"))
      (node (ref "DIGIT") (pin "9") (pinfunction "9_9") (pintype "passive"))
      (node (ref "Q3") (pin "1") (pinfunction "G_1") (pintype "passive"))
    )
    (net (code "31") (name "N$49") (class "Default")
      (node (ref "IC3") (pin "14") (pinfunction "X_14") (pintype "bidirectional"))
      (node (ref "MUSOR/NORMAL") (pin "2") (pinfunction "2_2") (pintype "passive"))
      (node (ref "R30") (pin "2") (pinfunction "2_2") (pintype "passive"))
      (node (ref "SJ5") (pin "2") (pinfunction "2_2") (pintype "passive"))
    )
    (net (code "32") (name "N$50") (class "Default")
      (node (ref "IC3") (pin "15") (pinfunction "Y_15") (pintype "bidirectional"))
      (node (ref "R28") (pin "2") (pinfunction "2_2") (pintype "passive"))
      (node (ref "SJ4") (pin "2") (pinfunction "2_2") (pintype "passive"))
    )
    (net (code "33") (name "Net-(C1-Pad+)") (class "Default")
      (node (ref "C1") (pin "+") (pinfunction "+_+") (pintype "passive"))
      (node (ref "R1") (pin "1") (pinfunction "1_1") (pintype "passive"))
      (node (ref "R4") (pin "2") (pinfunction "2_2") (pintype "passive"))
    )
    (net (code "34") (name "Net-(C2-Pad2)") (class "Default")
      (node (ref "C2") (pin "2") (pinfunction "2_2") (pintype "passive"))
      (node (ref "R6") (pin "1") (pinfunction "1_1") (pintype "passive"))
    )
    (net (code "35") (name "Net-(C3-Pad2)") (class "Default")
      (node (ref "C3") (pin "2") (pinfunction "2_2") (pintype "passive"))
      (node (ref "R7") (pin "1") (pinfunction "1_1") (pintype "passive"))
    )
    (net (code "36") (name "Net-(C4-Pad2)") (class "Default")
      (node (ref "C4") (pin "2") (pinfunction "2_2") (pintype "passive"))
      (node (ref "R10") (pin "1") (pinfunction "1_1") (pintype "passive"))
    )
    (net (code "37") (name "Net-(C5-Pad2)") (class "Default")
      (node (ref "C5") (pin "2") (pinfunction "2_2") (pintype "passive"))
      (node (ref "R11") (pin "1") (pinfunction "1_1") (pintype "passive"))
      (node (ref "R8") (pin "2") (pinfunction "2_2") (pintype "passive"))
    )
    (net (code "38") (name "Net-(C6-Pad2)") (class "Default")
      (node (ref "C6") (pin "2") (pinfunction "2_2") (pintype "passive"))
      (node (ref "R8") (pin "1") (pinfunction "1_1") (pintype "passive"))
    )
    (net (code "39") (name "Net-(C11-Pad1)") (class "Default")
      (node (ref "C11") (pin "1") (pinfunction "1_1") (pintype "passive"))
      (node (ref "R16") (pin "2") (pinfunction "2_2") (pintype "passive"))
      (node (ref "R18") (pin "1") (pinfunction "1_1") (pintype "passive"))
    )
    (net (code "40") (name "Net-(C12-Pad1)") (class "Default")
      (node (ref "C12") (pin "1") (pinfunction "1_1") (pintype "passive"))
      (node (ref "R19") (pin "1") (pinfunction "1_1") (pintype "passive"))
    )
    (net (code "41") (name "Net-(C13-Pad1)") (class "Default")
      (node (ref "C13") (pin "1") (pinfunction "1_1") (pintype "passive"))
      (node (ref "R17") (pin "2") (pinfunction "2_2") (pintype "passive"))
      (node (ref "R19") (pin "2") (pinfunction "2_2") (pintype "passive"))
    )
    (net (code "42") (name "Net-(C20-Pad2)") (class "Default")
      (node (ref "C20") (pin "2") (pinfunction "2_2") (pintype "passive"))
      (node (ref "R34") (pin "1") (pinfunction "1_1") (pintype "passive"))
    )
    (net (code "43") (name "Net-(C21-Pad2)") (class "Default")
      (node (ref "C21") (pin "2") (pinfunction "2_2") (pintype "passive"))
      (node (ref "R35") (pin "1") (pinfunction "1_1") (pintype "passive"))
    )
    (net (code "44") (name "Net-(C63-Pad1)") (class "Default")
      (node (ref "C63") (pin "1") (pinfunction "1_1") (pintype "passive"))
      (node (ref "C65") (pin "+") (pinfunction "+_+") (pintype "passive"))
      (node (ref "L10") (pin "2") (pinfunction "2_2") (pintype "passive"))
      (node (ref "R52") (pin "2") (pinfunction "2_2") (pintype "passive"))
    )
    (net (code "45") (name "Net-(C64-Pad2)") (class "Default")
      (node (ref "C64") (pin "2") (pinfunction "2_2") (pintype "passive"))
      (node (ref "L11") (pin "2") (pinfunction "2_2") (pintype "passive"))
      (node (ref "L12") (pin "1") (pinfunction "1_1") (pintype "passive"))
      (node (ref "R53") (pin "1") (pinfunction "1_1") (pintype "passive"))
    )
    (net (code "46") (name "Net-(C66-Pad+)") (class "Default")
      (node (ref "C66") (pin "+") (pinfunction "+_+") (pintype "passive"))
      (node (ref "C70") (pin "2") (pinfunction "2_2") (pintype "passive"))
      (node (ref "L11") (pin "1") (pinfunction "1_1") (pintype "passive"))
    )
    (net (code "47") (name "Net-(C68-Pad1)") (class "Default")
      (node (ref "C68") (pin "1") (pinfunction "1_1") (pintype "passive"))
      (node (ref "SJ4") (pin "1") (pinfunction "1_1") (pintype "passive"))
    )
    (net (code "48") (name "Net-(C69-Pad1)") (class "Default")
      (node (ref "C69") (pin "1") (pinfunction "1_1") (pintype "passive"))
      (node (ref "SJ5") (pin "1") (pinfunction "1_1") (pintype "passive"))
    )
    (net (code "49") (name "Net-(C71-Pad1)") (class "Default")
      (node (ref "C71") (pin "1") (pinfunction "1_1") (pintype "passive"))
      (node (ref "R55") (pin "2") (pinfunction "2_2") (pintype "passive"))
      (node (ref "SD2") (pin "HACK") (pinfunction "HACK_HACK") (pintype "bidirectional"))
    )
    (net (code "50") (name "Net-(D1-C)") (class "Default")
      (node (ref "C12") (pin "2") (pinfunction "2_2") (pintype "passive"))
      (node (ref "D1") (pin "P$2") (pinfunction "C_P$2") (pintype "passive"))
      (node (ref "D11") (pin "2") (pinfunction "C_2") (pintype "passive"))
      (node (ref "D2") (pin "P$1") (pinfunction "A_P$1") (pintype "passive"))
      (node (ref "D20") (pin "1") (pinfunction "A_1") (pintype "passive"))
    )
    (net (code "51") (name "Net-(D4-C)") (class "Default")
      (node (ref "D4") (pin "P$2") (pinfunction "C_P$2") (pintype "passive"))
      (node (ref "D9") (pin "2") (pinfunction "C_2") (pintype "passive"))
      (node (ref "Q1") (pin "1") (pinfunction "G_1") (pintype "passive"))
      (node (ref "R38") (pin "2") (pinfunction "2_2") (pintype "passive"))
    )
    (net (code "52") (name "Net-(D10-A)") (class "Default")
      (node (ref "D10") (pin "1") (pinfunction "A_1") (pintype "passive"))
      (node (ref "D3") (pin "P$1") (pinfunction "A_P$1") (pintype "passive"))
      (node (ref "R26") (pin "2") (pinfunction "2_2") (pintype "passive"))
    )
    (net (code "53") (name "Net-(D10-C)") (class "Default")
      (node (ref "C17") (pin "1") (pinfunction "1_1") (pintype "passive"))
      (node (ref "D10") (pin "2") (pinfunction "C_2") (pintype "passive"))
      (node (ref "D3") (pin "P$2") (pinfunction "C_P$2") (pintype "passive"))
      (node (ref "R27") (pin "2") (pinfunction "2_2") (pintype "passive"))
    )
    (net (code "54") (name "Net-(D12-A)") (class "Default")
      (node (ref "D12") (pin "2") (pinfunction "A_2") (pintype "passive"))
      (node (ref "RJ2") (pin "8") (pinfunction "8_8") (pintype "passive"))
    )
    (net (code "55") (name "Net-(D13-A)") (class "Default")
      (node (ref "D13") (pin "2") (pinfunction "A_2") (pintype "passive"))
      (node (ref "DSUB1") (pin "8") (pinfunction "M_8") (pintype "passive"))
    )
    (net (code "56") (name "Net-(D14-C)") (class "Default")
      (node (ref "D14") (pin "1") (pinfunction "C_1") (pintype "passive"))
      (node (ref "JP1") (pin "1") (pinfunction "1_1") (pintype "passive"))
      (node (ref "L9") (pin "1") (pinfunction "1_1") (pintype "passive"))
    )
    (net (code "57") (name "Net-(D16-C)") (class "Default")
      (node (ref "D16") (pin "P$2") (pinfunction "C_P$2") (pintype "passive"))
      (node (ref "D17") (pin "P$1") (pinfunction "A_P$1") (pintype "passive"))
      (node (ref "D7") (pin "2") (pinfunction "C_2") (pintype "passive"))
      (node (ref "D8") (pin "1") (pinfunction "A_1") (pintype "passive"))
    )
    (net (code "58") (name "Net-(D18-A)") (class "Default")
      (node (ref "D18") (pin "P$1") (pinfunction "A_P$1") (pintype "passive"))
      (node (ref "D19") (pin "P$2") (pinfunction "C_P$2") (pintype "passive"))
      (node (ref "D5") (pin "2") (pinfunction "C_2") (pintype "passive"))
      (node (ref "D6") (pin "1") (pinfunction "A_1") (pintype "passive"))
      (node (ref "R55") (pin "1") (pinfunction "1_1") (pintype "passive"))
    )
    (net (code "59") (name "Net-(D19-A)") (class "Default")
      (node (ref "C54") (pin "-") (pinfunction "-_-") (pintype "passive"))
      (node (ref "C55") (pin "2") (pinfunction "2_2") (pintype "passive"))
      (node (ref "D15") (pin "A") (pinfunction "A_A") (pintype "passive"))
      (node (ref "D19") (pin "P$1") (pinfunction "A_P$1") (pintype "passive"))
      (node (ref "D5") (pin "1") (pinfunction "A_1") (pintype "passive"))
      (node (ref "SJ1") (pin "2") (pinfunction "2_2") (pintype "passive"))
      (node (ref "SJ7") (pin "1") (pinfunction "1_1") (pintype "passive"))
    )
    (net (code "60") (name "Net-(F2-Pad2)") (class "Default")
      (node (ref "F2") (pin "2") (pinfunction "2_2") (pintype "passive"))
      (node (ref "L7") (pin "1") (pinfunction "1_1") (pintype "passive"))
    )
    (net (code "61") (name "Net-(F_LED-Pad2)") (class "Default")
      (node (ref "F_LED") (pin "2") (pinfunction "2_2") (pintype "passive"))
      (node (ref "R27") (pin "1") (pinfunction "1_1") (pintype "passive"))
    )
    (net (code "62") (name "Net-(HP_KIB-S)") (class "Default")
      (node (ref "C66") (pin "-") (pinfunction "-_-") (pintype "passive"))
      (node (ref "HP_KI") (pin "2") (pinfunction "S_2") (pintype "passive"))
      (node (ref "R56") (pin "1") (pinfunction "1_1") (pintype "passive"))
    )
    (net (code "63") (name "Net-(IC1A-+IN)") (class "Default")
      (node (ref "C10") (pin "1") (pinfunction "1_1") (pintype "passive"))
      (node (ref "IC1") (pin "3") (pinfunction "+IN_3") (pintype "input"))
      (node (ref "R10") (pin "2") (pinfunction "2_2") (pintype "passive"))
      (node (ref "R14") (pin "2") (pinfunction "2_2") (pintype "passive"))
    )
    (net (code "64") (name "Net-(IC1A--IN)") (class "Default")
      (node (ref "C6") (pin "1") (pinfunction "1_1") (pintype "passive"))
      (node (ref "C8") (pin "2") (pinfunction "2_2") (pintype "passive"))
      (node (ref "IC1") (pin "2") (pinfunction "-IN_2") (pintype "input"))
      (node (ref "R11") (pin "2") (pinfunction "2_2") (pintype "passive"))
      (node (ref "R12") (pin "1") (pinfunction "1_1") (pintype "passive"))
    )
    (net (code "65") (name "Net-(IC1B-+IN)") (class "Default")
      (node (ref "FENYELL") (pin "2") (pinfunction "2_2") (pintype "passive"))
      (node (ref "IC1") (pin "5") (pinfunction "+IN_5") (pintype "input"))
      (node (ref "Q1") (pin "3") (pinfunction "D_3") (pintype "passive"))
      (node (ref "R18") (pin "2") (pinfunction "2_2") (pintype "passive"))
    )
    (net (code "66") (name "Net-(IC1B--IN)") (class "Default")
      (node (ref "C14") (pin "2") (pinfunction "2_2") (pintype "passive"))
      (node (ref "IC1") (pin "6") (pinfunction "-IN_6") (pintype "input"))
      (node (ref "R20") (pin "2") (pinfunction "2_2") (pintype "passive"))
      (node (ref "R21") (pin "1") (pinfunction "1_1") (pintype "passive"))
    )
    (net (code "67") (name "Net-(IC1B-OUT)") (class "Default")
      (node (ref "C14") (pin "1") (pinfunction "1_1") (pintype "passive"))
      (node (ref "C15") (pin "2") (pinfunction "2_2") (pintype "passive"))
      (node (ref "IC1") (pin "7") (pinfunction "OUT_7") (pintype "output"))
      (node (ref "IC2") (pin "3") (pinfunction "+IN_3") (pintype "input"))
      (node (ref "R21") (pin "2") (pinfunction "2_2") (pintype "passive"))
    )
    (net (code "68") (name "Net-(IC2A--IN)") (class "Default")
      (node (ref "C16") (pin "2") (pinfunction "2_2") (pintype "passive"))
      (node (ref "IC2") (pin "2") (pinfunction "-IN_2") (pintype "input"))
      (node (ref "R22") (pin "2") (pinfunction "2_2") (pintype "passive"))
      (node (ref "R23") (pin "1") (pinfunction "1_1") (pintype "passive"))
    )
    (net (code "69") (name "Net-(IC2A-OUT)") (class "Default")
      (node (ref "C16") (pin "1") (pinfunction "1_1") (pintype "passive"))
      (node (ref "IC2") (pin "1") (pinfunction "OUT_1") (pintype "output"))
      (node (ref "LED1") (pin "K") (pinfunction "C_K") (pintype "passive"))
      (node (ref "R25") (pin "2") (pinfunction "2_2") (pintype "passive"))
      (node (ref "R26") (pin "1") (pinfunction "1_1") (pintype "passive"))
    )
    (net (code "70") (name "Net-(IC2B-+IN)") (class "Default")
      (node (ref "C7") (pin "1") (pinfunction "1_1") (pintype "passive"))
      (node (ref "IC2") (pin "5") (pinfunction "+IN_5") (pintype "input"))
      (node (ref "R6") (pin "2") (pinfunction "2_2") (pintype "passive"))
      (node (ref "R9") (pin "2") (pinfunction "2_2") (pintype "passive"))
    )
    (net (code "71") (name "Net-(IC2B--IN)") (class "Default")
      (node (ref "C9") (pin "2") (pinfunction "2_2") (pintype "passive"))
      (node (ref "IC2") (pin "6") (pinfunction "-IN_6") (pintype "input"))
      (node (ref "R13") (pin "1") (pinfunction "1_1") (pintype "passive"))
      (node (ref "R7") (pin "2") (pinfunction "2_2") (pintype "passive"))
    )
    (net (code "72") (name "Net-(IC2B-OUT)") (class "Default")
      (node (ref "C9") (pin "1") (pinfunction "1_1") (pintype "passive"))
      (node (ref "IC2") (pin "7") (pinfunction "OUT_7") (pintype "output"))
      (node (ref "R13") (pin "2") (pinfunction "2_2") (pintype "passive"))
      (node (ref "R17") (pin "1") (pinfunction "1_1") (pintype "passive"))
    )
    (net (code "73") (name "Net-(IC3A-INH)") (class "Default")
      (node (ref "IC3") (pin "6") (pinfunction "INH_6") (pintype "input"))
      (node (ref "Q3") (pin "3") (pinfunction "D_3") (pintype "passive"))
      (node (ref "R54") (pin "1") (pinfunction "1_1") (pintype "passive"))
    )
    (net (code "74") (name "Net-(IC3A-Y0)") (class "Default")
      (node (ref "IC3") (pin "2") (pinfunction "Y0_2") (pintype "bidirectional"))
      (node (ref "IC3") (pin "4") (pinfunction "Z_4") (pintype "bidirectional"))
    )
    (net (code "75") (name "Net-(IC4A-+IN)") (class "Default")
      (node (ref "C15") (pin "1") (pinfunction "1_1") (pintype "passive"))
      (node (ref "IC4") (pin "3") (pinfunction "+IN_3") (pintype "input"))
      (node (ref "R24") (pin "2") (pinfunction "2_2") (pintype "passive"))
      (node (ref "R29") (pin "2") (pinfunction "2_2") (pintype "passive"))
    )
    (net (code "76") (name "Net-(IC4A--IN)") (class "Default")
      (node (ref "C18") (pin "2") (pinfunction "2_2") (pintype "passive"))
      (node (ref "IC4") (pin "2") (pinfunction "-IN_2") (pintype "input"))
      (node (ref "R31") (pin "2") (pinfunction "2_2") (pintype "passive"))
      (node (ref "R32") (pin "1") (pinfunction "1_1") (pintype "passive"))
    )
    (net (code "77") (name "Net-(IC4A-OUT)") (class "Default")
      (node (ref "C18") (pin "1") (pinfunction "1_1") (pintype "passive"))
      (node (ref "C20") (pin "1") (pinfunction "1_1") (pintype "passive"))
      (node (ref "IC4") (pin "1") (pinfunction "OUT_1") (pintype "output"))
      (node (ref "R32") (pin "2") (pinfunction "2_2") (pintype "passive"))
    )
    (net (code "78") (name "Net-(IC4B--IN)") (class "Default")
      (node (ref "C19") (pin "2") (pinfunction "2_2") (pintype "passive"))
      (node (ref "IC4") (pin "6") (pinfunction "-IN_6") (pintype "input"))
      (node (ref "R29") (pin "1") (pinfunction "1_1") (pintype "passive"))
      (node (ref "R33") (pin "1") (pinfunction "1_1") (pintype "passive"))
    )
    (net (code "79") (name "Net-(IC4B-OUT)") (class "Default")
      (node (ref "C19") (pin "1") (pinfunction "1_1") (pintype "passive"))
      (node (ref "C21") (pin "1") (pinfunction "1_1") (pintype "passive"))
      (node (ref "IC4") (pin "7") (pinfunction "OUT_7") (pintype "output"))
      (node (ref "R33") (pin "2") (pinfunction "2_2") (pintype "passive"))
    )
    (net (code "80") (name "Net-(IC11-BSL)") (class "Default")
      (node (ref "C61") (pin "1") (pinfunction "1_1") (pintype "passive"))
      (node (ref "IC11") (pin "21") (pinfunction "BSL_21") (pintype "passive"))
    )
    (net (code "81") (name "Net-(IC11-BSR)") (class "Default")
      (node (ref "C60") (pin "1") (pinfunction "1_1") (pintype "passive"))
      (node (ref "IC11") (pin "16") (pinfunction "BSR_16") (pintype "passive"))
    )
    (net (code "82") (name "Net-(IC11-BYPASS)") (class "Default")
      (node (ref "C56") (pin "1") (pinfunction "1_1") (pintype "passive"))
      (node (ref "IC11") (pin "7") (pinfunction "BYPASS_7") (pintype "input"))
    )
    (net (code "83") (name "Net-(IC11-GAIN0)") (class "Default")
      (node (ref "IC11") (pin "18") (pinfunction "GAIN0_18") (pintype "input"))
      (node (ref "SJ2") (pin "2") (pinfunction "2_2") (pintype "passive"))
    )
    (net (code "84") (name "Net-(IC11-LIN)") (class "Default")
      (node (ref "C69") (pin "2") (pinfunction "2_2") (pintype "passive"))
      (node (ref "IC11") (pin "5") (pinfunction "LIN_5") (pintype "input"))
    )
    (net (code "85") (name "Net-(IC11-MUTE)") (class "Default")
      (node (ref "IC11") (pin "4") (pinfunction "MUTE_4") (pintype "input"))
      (node (ref "SJ8") (pin "1") (pinfunction "1_1") (pintype "passive"))
    )
    (net (code "86") (name "Net-(IC11-RIN)") (class "Default")
      (node (ref "C68") (pin "2") (pinfunction "2_2") (pintype "passive"))
      (node (ref "IC11") (pin "6") (pinfunction "RIN_6") (pintype "input"))
    )
    (net (code "87") (name "Net-(IC11-VCLAMP)") (class "Default")
      (node (ref "C59") (pin "1") (pinfunction "1_1") (pintype "passive"))
      (node (ref "IC11") (pin "11") (pinfunction "VCLAMP_11") (pintype "input"))
    )
    (net (code "88") (name "Net-(LAMPAB-S)") (class "Default")
      (node (ref "LAMPA") (pin "2") (pinfunction "S_2") (pintype "passive"))
      (node (ref "T2") (pin "2") (pinfunction "C_2") (pintype "passive"))
    )
    (net (code "89") (name "Net-(LED1-PadA)") (class "Default")
      (node (ref "LED1") (pin "A") (pinfunction "A_A") (pintype "passive"))
      (node (ref "R23") (pin "2") (pinfunction "2_2") (pintype "passive"))
      (node (ref "R25") (pin "1") (pinfunction "1_1") (pintype "passive"))
    )
    (net (code "90") (name "Net-(PROG-Pad4)") (class "Default")
      (node (ref "PROG") (pin "4") (pinfunction "4_4") (pintype "passive"))
      (node (ref "R36") (pin "2") (pinfunction "2_2") (pintype "passive"))
    )
    (net (code "91") (name "Net-(PROG-Pad8)") (class "Default")
      (node (ref "PROG") (pin "8") (pinfunction "8_8") (pintype "passive"))
      (node (ref "R37") (pin "2") (pinfunction "2_2") (pintype "passive"))
    )
    (net (code "92") (name "Net-(SD2-CTRL)") (class "Default")
      (node (ref "C48") (pin "1") (pinfunction "1_1") (pintype "passive"))
      (node (ref "C49") (pin "+") (pinfunction "+_+") (pintype "passive"))
      (node (ref "R47") (pin "2") (pinfunction "2_2") (pintype "passive"))
      (node (ref "SD2") (pin "CONTROL") (pinfunction "CTRL_CONTROL") (pintype "bidirectional"))
    )
    (net (code "93") (name "Net-(SD2-IN+)") (class "Default")
      (node (ref "C22") (pin "+") (pinfunction "+_+") (pintype "passive"))
      (node (ref "C47") (pin "+") (pinfunction "+_+") (pintype "passive"))
      (node (ref "L7") (pin "2") (pinfunction "2_2") (pintype "passive"))
      (node (ref "SD2") (pin "INPUT+") (pinfunction "IN+_INPUT+") (pintype "bidirectional"))
    )
    (net (code "94") (name "Net-(SD2-IN-)") (class "Default")
      (node (ref "C22") (pin "-") (pinfunction "-_-") (pintype "passive"))
      (node (ref "C47") (pin "-") (pinfunction "-_-") (pintype "passive"))
      (node (ref "C48") (pin "2") (pinfunction "2_2") (pintype "passive"))
      (node (ref "C49") (pin "-") (pinfunction "-_-") (pintype "passive"))
      (node (ref "L8") (pin "2") (pinfunction "2_2") (pintype "passive"))
      (node (ref "R47") (pin "1") (pinfunction "1_1") (pintype "passive"))
      (node (ref "SD2") (pin "INPUT-") (pinfunction "IN-_INPUT-") (pintype "bidirectional"))
    )
    (net (code "95") (name "Net-(SD2-PadOUT-)") (class "Default")
      (node (ref "SD2") (pin "OUT-") (pinfunction "OUT-_OUT-") (pintype "bidirectional"))
      (node (ref "SJ7") (pin "2") (pinfunction "2_2") (pintype "passive"))
    )
    (net (code "96") (name "Net-(SP_KIB-S)") (class "Default")
      (node (ref "C65") (pin "-") (pinfunction "-_-") (pintype "passive"))
      (node (ref "SP_KI") (pin "2") (pinfunction "S_2") (pintype "passive"))
    )
    (net (code "97") (name "Net-(T2-E)") (class "Default")
      (node (ref "R50") (pin "1") (pinfunction "1_1") (pintype "passive"))
      (node (ref "T2") (pin "3") (pinfunction "E_3") (pintype "passive"))
    )
    (net (code "98") (name "OUT+") (class "Default")
      (node (ref "DSUB1") (pin "4") (pinfunction "M_4") (pintype "passive"))
      (node (ref "R34") (pin "2") (pinfunction "2_2") (pintype "passive"))
      (node (ref "RJ2") (pin "6") (pinfunction "6_6") (pintype "passive"))
    )
    (net (code "99") (name "OUT-") (class "Default")
      (node (ref "DSUB1") (pin "5") (pinfunction "M_5") (pintype "passive"))
      (node (ref "R35") (pin "2") (pinfunction "2_2") (pintype "passive"))
      (node (ref "RJ2") (pin "3") (pinfunction "3_3") (pintype "passive"))
    )
    (net (code "100") (name "POTI_JEL") (class "Default")
      (node (ref "C13") (pin "2") (pinfunction "2_2") (pintype "passive"))
      (node (ref "POTI") (pin "7") (pinfunction "7_7") (pintype "passive"))
      (node (ref "POTI") (pin "8") (pinfunction "8_8") (pintype "passive"))
    )
    (net (code "101") (name "SP") (class "Default")
      (node (ref "MUSOR/NORMAL") (pin "5") (pinfunction "5_5") (pintype "passive"))
      (node (ref "POTI") (pin "10") (pinfunction "10_10") (pintype "passive"))
      (node (ref "POTI") (pin "9") (pinfunction "9_9") (pintype "passive"))
    )
    (net (code "102") (name "SPM") (class "Default")
      (node (ref "DIGIT") (pin "5") (pinfunction "5_5") (pintype "passive"))
      (node (ref "DIGIT") (pin "6") (pinfunction "6_6") (pintype "passive"))
      (node (ref "IC3") (pin "10") (pinfunction "B_10") (pintype "input"))
    )
    (net (code "103") (name "SPOUT") (class "Default")
      (node (ref "C60") (pin "2") (pinfunction "2_2") (pintype "passive"))
      (node (ref "C71") (pin "2") (pinfunction "2_2") (pintype "passive"))
      (node (ref "IC11") (pin "15") (pinfunction "ROUT_15") (pintype "output"))
      (node (ref "L10") (pin "1") (pinfunction "1_1") (pintype "passive"))
    )
    (net (code "104") (name "VDD") (class "Default")
      (node (ref "C26") (pin "1") (pinfunction "1_1") (pintype "passive"))
      (node (ref "C57") (pin "+") (pinfunction "+_+") (pintype "passive"))
      (node (ref "C58") (pin "1") (pinfunction "1_1") (pintype "passive"))
      (node (ref "IC1") (pin "8") (pinfunction "V+_8") (pintype "power_in"))
      (node (ref "IC11") (pin "19") (pinfunction "AVCC_19") (pintype "input"))
      (node (ref "IC11") (pin "20") (pinfunction "AVCC_20") (pintype "input"))
      (node (ref "IC2") (pin "8") (pinfunction "V+_8") (pintype "power_in"))
      (node (ref "IC4") (pin "8") (pinfunction "V+_8") (pintype "power_in"))
      (node (ref "R1") (pin "2") (pinfunction "2_2") (pintype "passive"))
      (node (ref "R51") (pin "1") (pinfunction "1_1") (pintype "passive"))
      (node (ref "SJ2") (pin "1") (pinfunction "1_1") (pintype "passive"))
    )
    (net (code "105") (name "VSS") (class "Default")
      (node (ref "C27") (pin "2") (pinfunction "2_2") (pintype "passive"))
      (node (ref "IC1") (pin "4") (pinfunction "V-_4") (pintype "power_in"))
      (node (ref "IC2") (pin "4") (pinfunction "V-_4") (pintype "power_in"))
      (node (ref "IC3") (pin "7") (pinfunction "VEE_7") (pintype "power_in"))
      (node (ref "IC4") (pin "4") (pinfunction "V-_4") (pintype "power_in"))
      (node (ref "SJ1") (pin "1") (pinfunction "1_1") (pintype "passive"))
    )
    (net (code "106") (name "X0") (class "Default")
      (node (ref "IC3") (pin "12") (pinfunction "X0_12") (pintype "bidirectional"))
      (node (ref "MUSOR/NORMAL") (pin "3") (pinfunction "3_3") (pintype "passive"))
    )
    (net (code "107") (name "unconnected-(IC12-GND-Pad2)") (class "Default")
      (node (ref "IC12") (pin "2") (pinfunction "GND_2") (pintype "passive"))
    )
    (net (code "108") (name "unconnected-(IC12-VI-Pad1)") (class "Default")
      (node (ref "IC12") (pin "1") (pinfunction "VI_1") (pintype "input"))
    )
    (net (code "109") (name "unconnected-(IC12-VO-Pad3)") (class "Default")
      (node (ref "IC12") (pin "3") (pinfunction "VO_3") (pintype "passive"))
    )
    (net (code "110") (name "unconnected-(POTI-Pad4)") (class "Default")
      (node (ref "POTI") (pin "4") (pinfunction "4_4") (pintype "passive"))
    )
    (net (code "111") (name "unconnected-(SD2-PadSZAB)") (class "Default")
      (node (ref "SD2") (pin "SZAB") (pinfunction "SZAB_SZAB") (pintype "bidirectional"))
    )
    (net (code "112") (name "~{MCLR}") (class "Default")
      (node (ref "PROG") (pin "5") (pinfunction "5_5") (pintype "passive"))
      (node (ref "TAP") (pin "1") (pinfunction "1_1") (pintype "passive"))
      (node (ref "TAP") (pin "2") (pinfunction "2_2") (pintype "passive"))
    )
  )
)
